# radiation.net
KiCad netlist of a schematic drawn in EAGLE
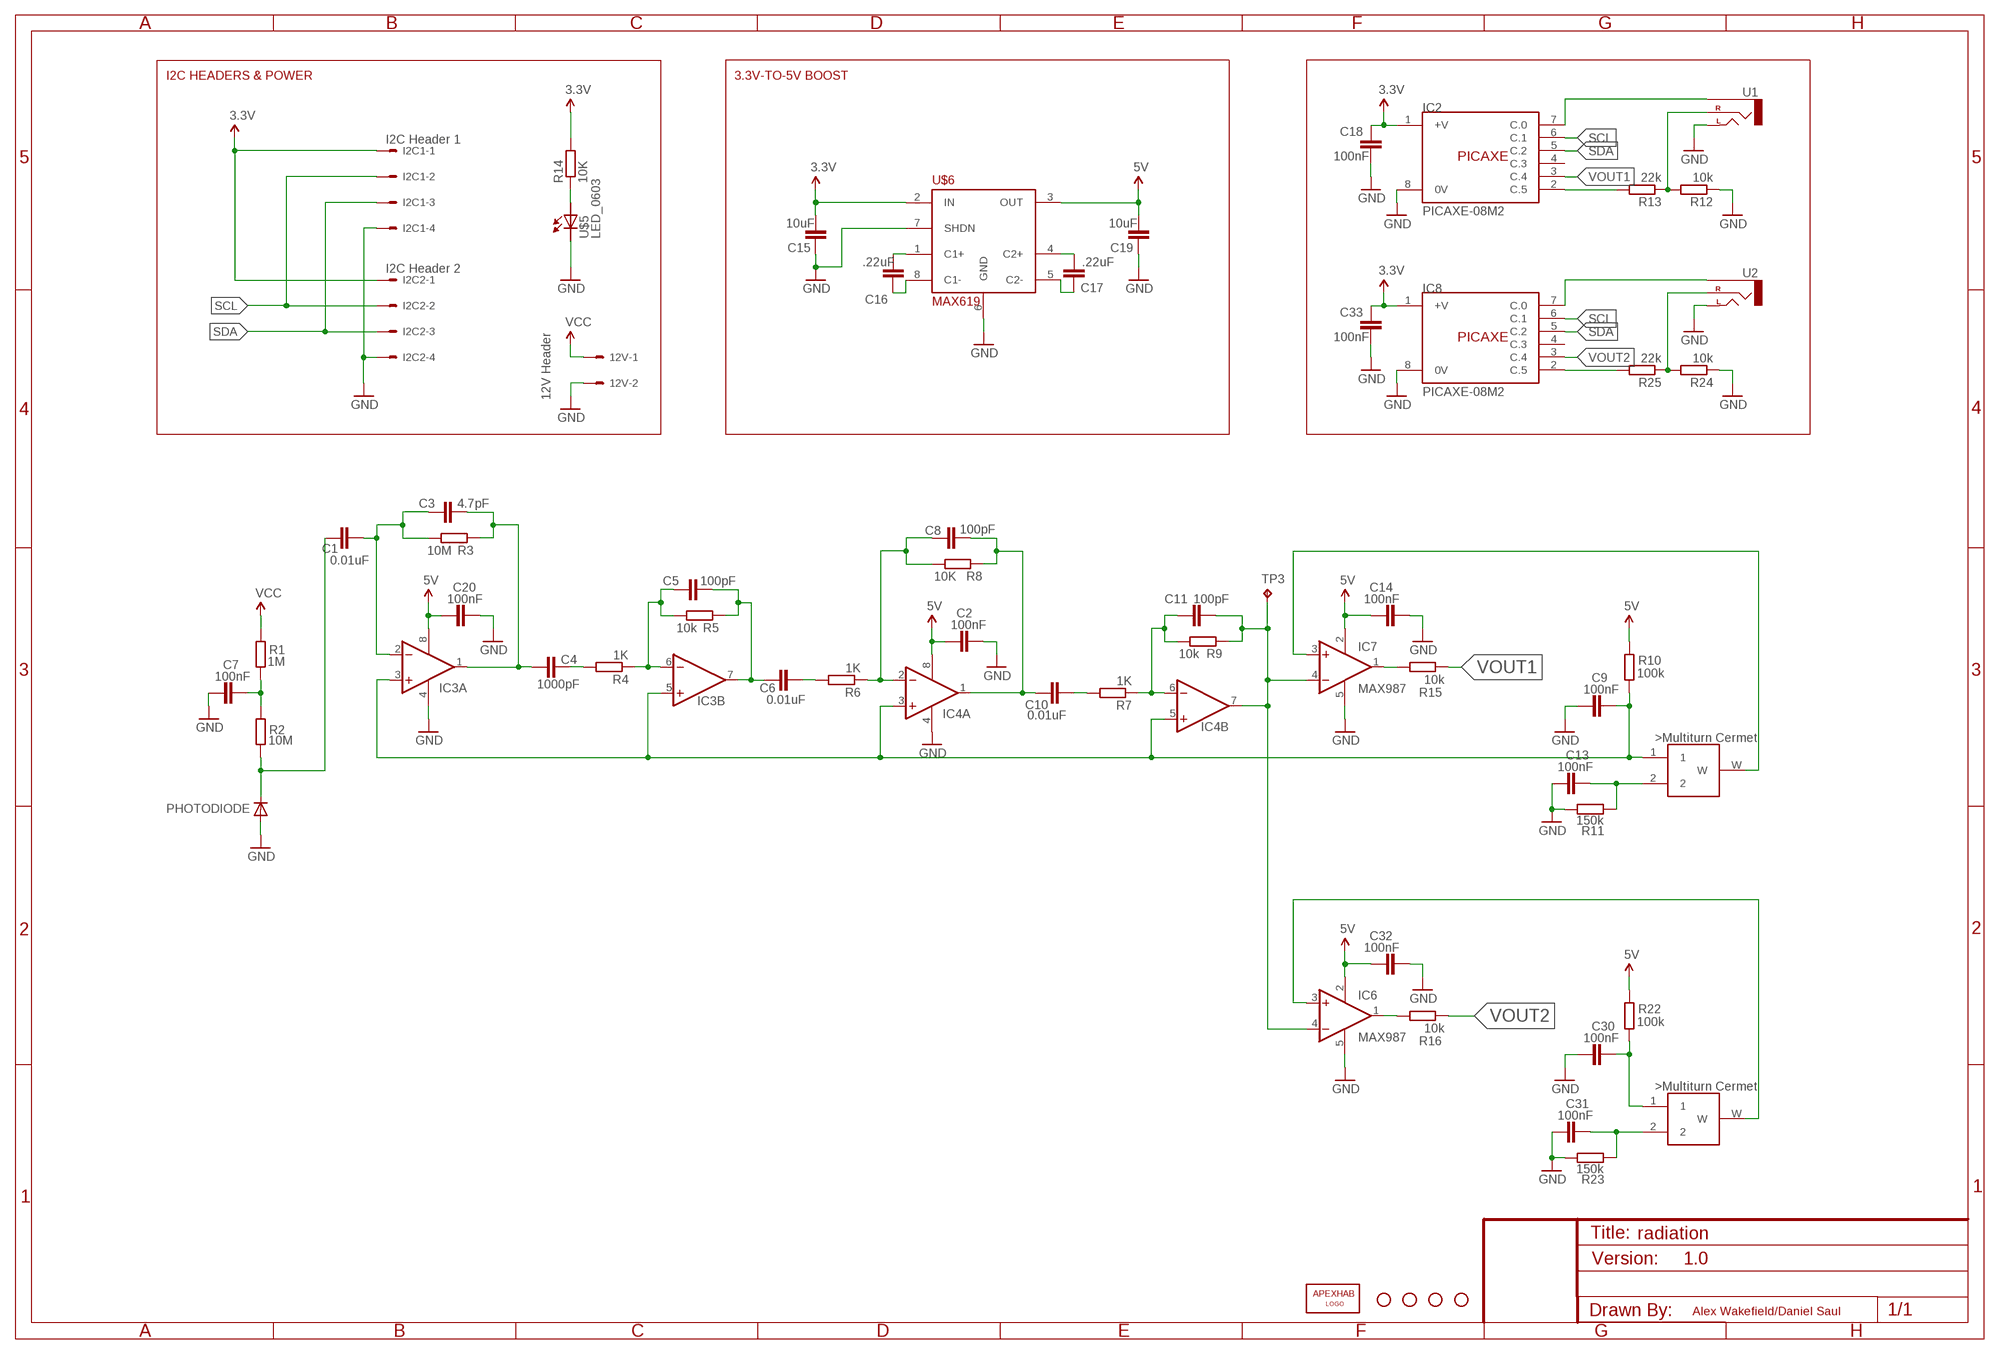
[diagram p0: schematic, sheet 1]

(export (version "E")
  (design (tool "Eeschema 10.0.6"))
  (components
    (comp (ref "12V")
      (value "12V Header")
      (footprint "eagle-import:6410-02")
      (libsource (lib "eagle-import") (part "22-?-0227-2021"))
    )
    (comp (ref "C1")
      (value "0.01uF")
      (footprint "eagle-import:C0805")
      (libsource (lib "eagle-import") (part "C-EUC0805"))
    )
    (comp (ref "C2")
      (value "100nF")
      (footprint "eagle-import:C0805")
      (libsource (lib "eagle-import") (part "C-EUC0805"))
    )
    (comp (ref "C3")
      (value "4.7pF")
      (footprint "eagle-import:C0805")
      (libsource (lib "eagle-import") (part "C-EUC0805"))
    )
    (comp (ref "C4")
      (value "1000pF")
      (footprint "eagle-import:C0805")
      (libsource (lib "eagle-import") (part "C-EUC0805"))
    )
    (comp (ref "C5")
      (value "100pF")
      (footprint "eagle-import:C0805")
      (libsource (lib "eagle-import") (part "C-EUC0805"))
    )
    (comp (ref "C6")
      (value "0.01uF")
      (footprint "eagle-import:C0805")
      (libsource (lib "eagle-import") (part "C-EUC0805"))
    )
    (comp (ref "C7")
      (value "100nF")
      (footprint "eagle-import:C0805")
      (libsource (lib "eagle-import") (part "C-EUC0805"))
    )
    (comp (ref "C8")
      (value "100pF")
      (footprint "eagle-import:C0805")
      (libsource (lib "eagle-import") (part "C-EUC0805"))
    )
    (comp (ref "C9")
      (value "100nF")
      (footprint "eagle-import:C0805")
      (libsource (lib "eagle-import") (part "C-EUC0805"))
    )
    (comp (ref "C10")
      (value "0.01uF")
      (footprint "eagle-import:C0805")
      (libsource (lib "eagle-import") (part "C-EUC0805"))
    )
    (comp (ref "C11")
      (value "100pF")
      (footprint "eagle-import:C0805")
      (libsource (lib "eagle-import") (part "C-EUC0805"))
    )
    (comp (ref "C13")
      (value "100nF")
      (footprint "eagle-import:C0805")
      (libsource (lib "eagle-import") (part "C-EUC0805"))
    )
    (comp (ref "C14")
      (value "100nF")
      (footprint "eagle-import:C0805")
      (libsource (lib "eagle-import") (part "C-EUC0805"))
    )
    (comp (ref "C15")
      (value "10uF")
      (footprint "eagle-import:C0805")
      (libsource (lib "eagle-import") (part "C-EUC0805"))
    )
    (comp (ref "C16")
      (value ".22uF")
      (footprint "eagle-import:C0805")
      (libsource (lib "eagle-import") (part "C-EUC0805"))
    )
    (comp (ref "C17")
      (value ".22uF")
      (footprint "eagle-import:C0805")
      (libsource (lib "eagle-import") (part "C-EUC0805"))
    )
    (comp (ref "C18")
      (value "100nF")
      (footprint "eagle-import:C0805")
      (libsource (lib "eagle-import") (part "C-EUC0805"))
    )
    (comp (ref "C19")
      (value "10uF")
      (footprint "eagle-import:C0805")
      (libsource (lib "eagle-import") (part "C-EUC0805"))
    )
    (comp (ref "C20")
      (value "100nF")
      (footprint "eagle-import:C0805")
      (libsource (lib "eagle-import") (part "C-EUC0805"))
    )
    (comp (ref "C30")
      (value "100nF")
      (footprint "eagle-import:C0805")
      (libsource (lib "eagle-import") (part "C-EUC0805"))
    )
    (comp (ref "C31")
      (value "100nF")
      (footprint "eagle-import:C0805")
      (libsource (lib "eagle-import") (part "C-EUC0805"))
    )
    (comp (ref "C32")
      (value "100nF")
      (footprint "eagle-import:C0805")
      (libsource (lib "eagle-import") (part "C-EUC0805"))
    )
    (comp (ref "C33")
      (value "100nF")
      (footprint "eagle-import:C0805")
      (libsource (lib "eagle-import") (part "C-EUC0805"))
    )
    (comp (ref "I2C1")
      (value "I2C Header 1")
      (footprint "eagle-import:6410-04")
      (libsource (lib "eagle-import") (part "22-?-0427-2041"))
    )
    (comp (ref "I2C2")
      (value "I2C Header 2")
      (footprint "eagle-import:6410-04")
      (libsource (lib "eagle-import") (part "22-?-0427-2041"))
    )
    (comp (ref "IC2")
      (value "PICAXE-08M2")
      (footprint "eagle-import:SOIC8")
      (libsource (lib "eagle-import") (part "PICAXE-08M2"))
    )
    (comp (ref "IC3")
      (value "max4477")
      (footprint "eagle-import:SO08")
      (libsource (lib "eagle-import") (part "CA3240ED"))
    )
    (comp (ref "IC4")
      (value "<AX4477")
      (footprint "eagle-import:SO08")
      (libsource (lib "eagle-import") (part "CA3240ED"))
    )
    (comp (ref "IC6")
      (value "MAX987")
      (footprint "eagle-import:SOT23-5")
      (libsource (lib "eagle-import") (part "MCP601R"))
    )
    (comp (ref "IC7")
      (value "MAX987")
      (footprint "eagle-import:SOT23-5")
      (libsource (lib "eagle-import") (part "MCP601R"))
    )
    (comp (ref "IC8")
      (value "PICAXE-08M2")
      (footprint "eagle-import:SOIC8")
      (libsource (lib "eagle-import") (part "PICAXE-08M2"))
    )
    (comp (ref "JP1")
      (value "APEXHAB-LOGO_APEX")
      (footprint "eagle-import:APEX-LOGO")
      (libsource (lib "eagle-import") (part "APEXHAB-LOGO_APEX"))
    )
    (comp (ref "JP2")
      (value "STAND-OFF")
      (footprint "eagle-import:STAND-OFF")
      (libsource (lib "eagle-import") (part "STAND-OFF"))
    )
    (comp (ref "JP3")
      (value "STAND-OFF")
      (footprint "eagle-import:STAND-OFF")
      (libsource (lib "eagle-import") (part "STAND-OFF"))
    )
    (comp (ref "JP4")
      (value "STAND-OFF")
      (footprint "eagle-import:STAND-OFF")
      (libsource (lib "eagle-import") (part "STAND-OFF"))
    )
    (comp (ref "JP5")
      (value "STAND-OFF")
      (footprint "eagle-import:STAND-OFF")
      (libsource (lib "eagle-import") (part "STAND-OFF"))
    )
    (comp (ref "PHOTODIODE")
      (value "DIODE-D-2.5")
      (footprint "eagle-import:D-2.5")
      (libsource (lib "eagle-import") (part "DIODE-D-2.5"))
    )
    (comp (ref "R1")
      (value "1M")
      (footprint "eagle-import:R0805")
      (libsource (lib "eagle-import") (part "R-EU_R0805"))
    )
    (comp (ref "R2")
      (value "10M")
      (footprint "eagle-import:R0805")
      (libsource (lib "eagle-import") (part "R-EU_R0805"))
    )
    (comp (ref "R3")
      (value "10M")
      (footprint "eagle-import:R0805")
      (libsource (lib "eagle-import") (part "R-EU_R0805"))
    )
    (comp (ref "R4")
      (value "1K")
      (footprint "eagle-import:R0805")
      (libsource (lib "eagle-import") (part "R-EU_R0805"))
    )
    (comp (ref "R5")
      (value "10k")
      (footprint "eagle-import:R0805")
      (libsource (lib "eagle-import") (part "R-EU_R0805"))
    )
    (comp (ref "R6")
      (value "1K")
      (footprint "eagle-import:R0805")
      (libsource (lib "eagle-import") (part "R-EU_R0805"))
    )
    (comp (ref "R7")
      (value "1K")
      (footprint "eagle-import:R0805")
      (libsource (lib "eagle-import") (part "R-EU_R0805"))
    )
    (comp (ref "R8")
      (value "10K")
      (footprint "eagle-import:R0805")
      (libsource (lib "eagle-import") (part "R-EU_R0805"))
    )
    (comp (ref "R9")
      (value "10k")
      (footprint "eagle-import:R0805")
      (libsource (lib "eagle-import") (part "R-EU_R0805"))
    )
    (comp (ref "R10")
      (value "100k")
      (footprint "eagle-import:R0805")
      (libsource (lib "eagle-import") (part "R-EU_R0805"))
    )
    (comp (ref "R11")
      (value "150k")
      (footprint "eagle-import:R0805")
      (libsource (lib "eagle-import") (part "R-EU_R0805"))
    )
    (comp (ref "R12")
      (value "10k")
      (footprint "eagle-import:R0805")
      (libsource (lib "eagle-import") (part "R-EU_R0805"))
    )
    (comp (ref "R13")
      (value "22k")
      (footprint "eagle-import:R0805")
      (libsource (lib "eagle-import") (part "R-EU_R0805"))
    )
    (comp (ref "R14")
      (value "10K")
      (footprint "eagle-import:R0805")
      (libsource (lib "eagle-import") (part "R-EU_R0805"))
    )
    (comp (ref "R15")
      (value "10k")
      (footprint "eagle-import:R0805")
      (libsource (lib "eagle-import") (part "R-EU_R0805"))
    )
    (comp (ref "R16")
      (value "10k")
      (footprint "eagle-import:R0805")
      (libsource (lib "eagle-import") (part "R-EU_R0805"))
    )
    (comp (ref "R22")
      (value "100k")
      (footprint "eagle-import:R0805")
      (libsource (lib "eagle-import") (part "R-EU_R0805"))
    )
    (comp (ref "R23")
      (value "150k")
      (footprint "eagle-import:R0805")
      (libsource (lib "eagle-import") (part "R-EU_R0805"))
    )
    (comp (ref "R24")
      (value "10k")
      (footprint "eagle-import:R0805")
      (libsource (lib "eagle-import") (part "R-EU_R0805"))
    )
    (comp (ref "R25")
      (value "22k")
      (footprint "eagle-import:R0805")
      (libsource (lib "eagle-import") (part "R-EU_R0805"))
    )
    (comp (ref "TP3")
      (value "TPTP10SQ")
      (footprint "eagle-import:TP10SQ")
      (libsource (lib "eagle-import") (part "TPTP10SQ"))
    )
    (comp (ref "U$3")
      (value "YL_SMT_11-TURN_CERMET_TRIMMER,_10K_0.25W")
      (footprint "eagle-import:YL_SMT_11-TURN_CERMET_TRIMMER,_10K_0.25W")
      (libsource (lib "eagle-import") (part "YL_SMT_11-TURN_CERMET_TRIMMER,_10K_0.25W"))
    )
    (comp (ref "U$4")
      (value "YL_SMT_11-TURN_CERMET_TRIMMER,_10K_0.25W")
      (footprint "eagle-import:YL_SMT_11-TURN_CERMET_TRIMMER,_10K_0.25W")
      (libsource (lib "eagle-import") (part "YL_SMT_11-TURN_CERMET_TRIMMER,_10K_0.25W"))
    )
    (comp (ref "U$5")
      (value "LED_0603")
      (footprint "eagle-import:CHIPLED_0603")
      (libsource (lib "eagle-import") (part "LED_0603"))
    )
    (comp (ref "U$6")
      (value "MAX619")
      (footprint "eagle-import:SO8")
      (libsource (lib "eagle-import") (part "MAX619"))
    )
    (comp (ref "U1")
      (value "AUDIO-JACKPTH")
      (footprint "eagle-import:AUDIO-JACK")
      (libsource (lib "eagle-import") (part "AUDIO-JACKPTH"))
    )
    (comp (ref "U2")
      (value "AUDIO-JACKPTH")
      (footprint "eagle-import:AUDIO-JACK")
      (libsource (lib "eagle-import") (part "AUDIO-JACKPTH"))
    )
  )
  (nets
    (net (code "1") (name "3.3V") (class "Default")
      (node (ref "C15") (pin "2") (pinfunction "2_2") (pintype "passive"))
      (node (ref "C18") (pin "1") (pinfunction "1_1") (pintype "passive"))
      (node (ref "C33") (pin "1") (pinfunction "1_1") (pintype "passive"))
      (node (ref "I2C1") (pin "1") (pinfunction "S_1") (pintype "passive"))
      (node (ref "I2C2") (pin "1") (pinfunction "S_1") (pintype "passive"))
      (node (ref "IC2") (pin "1") (pinfunction "+V_1") (pintype "power_in"))
      (node (ref "IC8") (pin "1") (pinfunction "+V_1") (pintype "power_in"))
      (node (ref "R14") (pin "2") (pinfunction "2_2") (pintype "passive"))
      (node (ref "U$6") (pin "2") (pinfunction "IN_2") (pintype "bidirectional"))
    )
    (net (code "2") (name "5V") (class "Default")
      (node (ref "C14") (pin "1") (pinfunction "1_1") (pintype "passive"))
      (node (ref "C19") (pin "2") (pinfunction "2_2") (pintype "passive"))
      (node (ref "C2") (pin "1") (pinfunction "1_1") (pintype "passive"))
      (node (ref "C20") (pin "1") (pinfunction "1_1") (pintype "passive"))
      (node (ref "C32") (pin "1") (pinfunction "1_1") (pintype "passive"))
      (node (ref "IC3") (pin "8") (pinfunction "V+_8") (pintype "power_in"))
      (node (ref "IC4") (pin "8") (pinfunction "V+_8") (pintype "power_in"))
      (node (ref "IC6") (pin "2") (pinfunction "V+_2") (pintype "power_in"))
      (node (ref "IC7") (pin "2") (pinfunction "V+_2") (pintype "power_in"))
      (node (ref "R10") (pin "1") (pinfunction "1_1") (pintype "passive"))
      (node (ref "R22") (pin "1") (pinfunction "1_1") (pintype "passive"))
      (node (ref "U$6") (pin "3") (pinfunction "OUT_3") (pintype "bidirectional"))
    )
    (net (code "3") (name "GND") (class "Default")
      (node (ref "12V") (pin "2") (pinfunction "S_2") (pintype "passive"))
      (node (ref "C13") (pin "1") (pinfunction "1_1") (pintype "passive"))
      (node (ref "C14") (pin "2") (pinfunction "2_2") (pintype "passive"))
      (node (ref "C15") (pin "1") (pinfunction "1_1") (pintype "passive"))
      (node (ref "C18") (pin "2") (pinfunction "2_2") (pintype "passive"))
      (node (ref "C19") (pin "1") (pinfunction "1_1") (pintype "passive"))
      (node (ref "C2") (pin "2") (pinfunction "2_2") (pintype "passive"))
      (node (ref "C20") (pin "2") (pinfunction "2_2") (pintype "passive"))
      (node (ref "C30") (pin "1") (pinfunction "1_1") (pintype "passive"))
      (node (ref "C31") (pin "1") (pinfunction "1_1") (pintype "passive"))
      (node (ref "C32") (pin "2") (pinfunction "2_2") (pintype "passive"))
      (node (ref "C33") (pin "2") (pinfunction "2_2") (pintype "passive"))
      (node (ref "C7") (pin "1") (pinfunction "1_1") (pintype "passive"))
      (node (ref "C9") (pin "1") (pinfunction "1_1") (pintype "passive"))
      (node (ref "I2C1") (pin "4") (pinfunction "S_4") (pintype "passive"))
      (node (ref "I2C2") (pin "4") (pinfunction "S_4") (pintype "passive"))
      (node (ref "IC2") (pin "8") (pinfunction "0V_8") (pintype "power_in"))
      (node (ref "IC3") (pin "4") (pinfunction "V-_4") (pintype "power_in"))
      (node (ref "IC4") (pin "4") (pinfunction "V-_4") (pintype "power_in"))
      (node (ref "IC6") (pin "5") (pinfunction "V-_5") (pintype "power_in"))
      (node (ref "IC7") (pin "5") (pinfunction "V-_5") (pintype "power_in"))
      (node (ref "IC8") (pin "8") (pinfunction "0V_8") (pintype "power_in"))
      (node (ref "PHOTODIODE") (pin "A") (pinfunction "A_A") (pintype "passive"))
      (node (ref "R11") (pin "2") (pinfunction "2_2") (pintype "passive"))
      (node (ref "R12") (pin "1") (pinfunction "1_1") (pintype "passive"))
      (node (ref "R23") (pin "2") (pinfunction "2_2") (pintype "passive"))
      (node (ref "R24") (pin "1") (pinfunction "1_1") (pintype "passive"))
      (node (ref "U$5") (pin "C") (pinfunction "C_C") (pintype "passive"))
      (node (ref "U$6") (pin "6") (pinfunction "GND_6") (pintype "bidirectional"))
      (node (ref "U$6") (pin "7") (pinfunction "SHDN_7") (pintype "bidirectional"))
      (node (ref "U1") (pin "TIP") (pinfunction "LEFT_TIP") (pintype "bidirectional"))
      (node (ref "U2") (pin "TIP") (pinfunction "LEFT_TIP") (pintype "bidirectional"))
    )
    (net (code "4") (name "Net-(C1-Pad1)") (class "Default")
      (node (ref "C1") (pin "1") (pinfunction "1_1") (pintype "passive"))
      (node (ref "PHOTODIODE") (pin "C") (pinfunction "C_C") (pintype "passive"))
      (node (ref "R2") (pin "1") (pinfunction "1_1") (pintype "passive"))
    )
    (net (code "5") (name "Net-(C4-Pad2)") (class "Default")
      (node (ref "C4") (pin "2") (pinfunction "2_2") (pintype "passive"))
      (node (ref "R4") (pin "2") (pinfunction "2_2") (pintype "passive"))
    )
    (net (code "6") (name "Net-(C6-Pad2)") (class "Default")
      (node (ref "C6") (pin "2") (pinfunction "2_2") (pintype "passive"))
      (node (ref "R6") (pin "2") (pinfunction "2_2") (pintype "passive"))
    )
    (net (code "7") (name "Net-(C7-Pad2)") (class "Default")
      (node (ref "C7") (pin "2") (pinfunction "2_2") (pintype "passive"))
      (node (ref "R1") (pin "1") (pinfunction "1_1") (pintype "passive"))
      (node (ref "R2") (pin "2") (pinfunction "2_2") (pintype "passive"))
    )
    (net (code "8") (name "Net-(C10-Pad2)") (class "Default")
      (node (ref "C10") (pin "2") (pinfunction "2_2") (pintype "passive"))
      (node (ref "R7") (pin "2") (pinfunction "2_2") (pintype "passive"))
    )
    (net (code "9") (name "Net-(C13-Pad2)") (class "Default")
      (node (ref "C13") (pin "2") (pinfunction "2_2") (pintype "passive"))
      (node (ref "R11") (pin "1") (pinfunction "1_1") (pintype "passive"))
      (node (ref "U$4") (pin "2") (pinfunction "2_2") (pintype "bidirectional"))
    )
    (net (code "10") (name "Net-(C30-Pad2)") (class "Default")
      (node (ref "C30") (pin "2") (pinfunction "2_2") (pintype "passive"))
      (node (ref "R22") (pin "2") (pinfunction "2_2") (pintype "passive"))
      (node (ref "U$3") (pin "1") (pinfunction "1_1") (pintype "bidirectional"))
    )
    (net (code "11") (name "Net-(C31-Pad2)") (class "Default")
      (node (ref "C31") (pin "2") (pinfunction "2_2") (pintype "passive"))
      (node (ref "R23") (pin "1") (pinfunction "1_1") (pintype "passive"))
      (node (ref "U$3") (pin "2") (pinfunction "2_2") (pintype "bidirectional"))
    )
    (net (code "12") (name "Net-(IC2-C.0)") (class "Default")
      (node (ref "IC2") (pin "7") (pinfunction "C.0_7") (pintype "bidirectional"))
      (node (ref "U1") (pin "SLEEVE") (pinfunction "SLEEVE_SLEEVE") (pintype "bidirectional"))
    )
    (net (code "13") (name "Net-(IC2-C.5)") (class "Default")
      (node (ref "IC2") (pin "2") (pinfunction "C.5_2") (pintype "bidirectional"))
      (node (ref "R13") (pin "2") (pinfunction "2_2") (pintype "passive"))
    )
    (net (code "14") (name "Net-(IC3A-+IN)") (class "Default")
      (node (ref "C9") (pin "2") (pinfunction "2_2") (pintype "passive"))
      (node (ref "IC3") (pin "3") (pinfunction "+IN_3") (pintype "input"))
      (node (ref "IC3") (pin "5") (pinfunction "+IN_5") (pintype "input"))
      (node (ref "IC4") (pin "3") (pinfunction "+IN_3") (pintype "input"))
      (node (ref "IC4") (pin "5") (pinfunction "+IN_5") (pintype "input"))
      (node (ref "R10") (pin "2") (pinfunction "2_2") (pintype "passive"))
      (node (ref "U$4") (pin "1") (pinfunction "1_1") (pintype "bidirectional"))
    )
    (net (code "15") (name "Net-(IC3A--IN)") (class "Default")
      (node (ref "C1") (pin "2") (pinfunction "2_2") (pintype "passive"))
      (node (ref "C3") (pin "1") (pinfunction "1_1") (pintype "passive"))
      (node (ref "IC3") (pin "2") (pinfunction "-IN_2") (pintype "input"))
      (node (ref "R3") (pin "2") (pinfunction "2_2") (pintype "passive"))
    )
    (net (code "16") (name "Net-(IC3A-OUT)") (class "Default")
      (node (ref "C3") (pin "2") (pinfunction "2_2") (pintype "passive"))
      (node (ref "C4") (pin "1") (pinfunction "1_1") (pintype "passive"))
      (node (ref "IC3") (pin "1") (pinfunction "OUT_1") (pintype "output"))
      (node (ref "R3") (pin "1") (pinfunction "1_1") (pintype "passive"))
    )
    (net (code "17") (name "Net-(IC3B--IN)") (class "Default")
      (node (ref "C5") (pin "1") (pinfunction "1_1") (pintype "passive"))
      (node (ref "IC3") (pin "6") (pinfunction "-IN_6") (pintype "input"))
      (node (ref "R4") (pin "1") (pinfunction "1_1") (pintype "passive"))
      (node (ref "R5") (pin "2") (pinfunction "2_2") (pintype "passive"))
    )
    (net (code "18") (name "Net-(IC3B-OUT)") (class "Default")
      (node (ref "C5") (pin "2") (pinfunction "2_2") (pintype "passive"))
      (node (ref "C6") (pin "1") (pinfunction "1_1") (pintype "passive"))
      (node (ref "IC3") (pin "7") (pinfunction "OUT_7") (pintype "output"))
      (node (ref "R5") (pin "1") (pinfunction "1_1") (pintype "passive"))
    )
    (net (code "19") (name "Net-(IC4A--IN)") (class "Default")
      (node (ref "C8") (pin "1") (pinfunction "1_1") (pintype "passive"))
      (node (ref "IC4") (pin "2") (pinfunction "-IN_2") (pintype "input"))
      (node (ref "R6") (pin "1") (pinfunction "1_1") (pintype "passive"))
      (node (ref "R8") (pin "2") (pinfunction "2_2") (pintype "passive"))
    )
    (net (code "20") (name "Net-(IC4A-OUT)") (class "Default")
      (node (ref "C10") (pin "1") (pinfunction "1_1") (pintype "passive"))
      (node (ref "C8") (pin "2") (pinfunction "2_2") (pintype "passive"))
      (node (ref "IC4") (pin "1") (pinfunction "OUT_1") (pintype "output"))
      (node (ref "R8") (pin "1") (pinfunction "1_1") (pintype "passive"))
    )
    (net (code "21") (name "Net-(IC4B--IN)") (class "Default")
      (node (ref "C11") (pin "1") (pinfunction "1_1") (pintype "passive"))
      (node (ref "IC4") (pin "6") (pinfunction "-IN_6") (pintype "input"))
      (node (ref "R7") (pin "1") (pinfunction "1_1") (pintype "passive"))
      (node (ref "R9") (pin "2") (pinfunction "2_2") (pintype "passive"))
    )
    (net (code "22") (name "Net-(IC4B-OUT)") (class "Default")
      (node (ref "C11") (pin "2") (pinfunction "2_2") (pintype "passive"))
      (node (ref "IC4") (pin "7") (pinfunction "OUT_7") (pintype "output"))
      (node (ref "IC6") (pin "4") (pinfunction "-IN_4") (pintype "input"))
      (node (ref "IC7") (pin "4") (pinfunction "-IN_4") (pintype "input"))
      (node (ref "R9") (pin "1") (pinfunction "1_1") (pintype "passive"))
      (node (ref "TP3") (pin "TP") (pinfunction "TP_TP") (pintype "input"))
    )
    (net (code "23") (name "Net-(IC6-+IN)") (class "Default")
      (node (ref "IC6") (pin "3") (pinfunction "+IN_3") (pintype "input"))
      (node (ref "U$3") (pin "W") (pinfunction "W_W") (pintype "bidirectional"))
    )
    (net (code "24") (name "Net-(IC6-OUT)") (class "Default")
      (node (ref "IC6") (pin "1") (pinfunction "OUT_1") (pintype "output"))
      (node (ref "R16") (pin "2") (pinfunction "2_2") (pintype "passive"))
    )
    (net (code "25") (name "Net-(IC7-+IN)") (class "Default")
      (node (ref "IC7") (pin "3") (pinfunction "+IN_3") (pintype "input"))
      (node (ref "U$4") (pin "W") (pinfunction "W_W") (pintype "bidirectional"))
    )
    (net (code "26") (name "Net-(IC7-OUT)") (class "Default")
      (node (ref "IC7") (pin "1") (pinfunction "OUT_1") (pintype "output"))
      (node (ref "R15") (pin "2") (pinfunction "2_2") (pintype "passive"))
    )
    (net (code "27") (name "Net-(IC8-C.0)") (class "Default")
      (node (ref "IC8") (pin "7") (pinfunction "C.0_7") (pintype "bidirectional"))
      (node (ref "U2") (pin "SLEEVE") (pinfunction "SLEEVE_SLEEVE") (pintype "bidirectional"))
    )
    (net (code "28") (name "Net-(IC8-C.5)") (class "Default")
      (node (ref "IC8") (pin "2") (pinfunction "C.5_2") (pintype "bidirectional"))
      (node (ref "R25") (pin "2") (pinfunction "2_2") (pintype "passive"))
    )
    (net (code "29") (name "Net-(R14-Pad1)") (class "Default")
      (node (ref "R14") (pin "1") (pinfunction "1_1") (pintype "passive"))
      (node (ref "U$5") (pin "A") (pinfunction "A_A") (pintype "passive"))
    )
    (net (code "30") (name "Net-(U$6-C1+)") (class "Default")
      (node (ref "C16") (pin "2") (pinfunction "2_2") (pintype "passive"))
      (node (ref "U$6") (pin "1") (pinfunction "C1+_1") (pintype "bidirectional"))
    )
    (net (code "31") (name "Net-(U$6-C1-)") (class "Default")
      (node (ref "C16") (pin "1") (pinfunction "1_1") (pintype "passive"))
      (node (ref "U$6") (pin "8") (pinfunction "C1-_8") (pintype "bidirectional"))
    )
    (net (code "32") (name "Net-(U$6-C2+)") (class "Default")
      (node (ref "C17") (pin "2") (pinfunction "2_2") (pintype "passive"))
      (node (ref "U$6") (pin "4") (pinfunction "C2+_4") (pintype "bidirectional"))
    )
    (net (code "33") (name "Net-(U$6-C2-)") (class "Default")
      (node (ref "C17") (pin "1") (pinfunction "1_1") (pintype "passive"))
      (node (ref "U$6") (pin "5") (pinfunction "C2-_5") (pintype "bidirectional"))
    )
    (net (code "34") (name "Net-(U1-RIGHT)") (class "Default")
      (node (ref "R12") (pin "2") (pinfunction "2_2") (pintype "passive"))
      (node (ref "R13") (pin "1") (pinfunction "1_1") (pintype "passive"))
      (node (ref "U1") (pin "RING") (pinfunction "RIGHT_RING") (pintype "bidirectional"))
    )
    (net (code "35") (name "Net-(U2-RIGHT)") (class "Default")
      (node (ref "R24") (pin "2") (pinfunction "2_2") (pintype "passive"))
      (node (ref "R25") (pin "1") (pinfunction "1_1") (pintype "passive"))
      (node (ref "U2") (pin "RING") (pinfunction "RIGHT_RING") (pintype "bidirectional"))
    )
    (net (code "36") (name "SCL") (class "Default")
      (node (ref "I2C1") (pin "2") (pinfunction "S_2") (pintype "passive"))
      (node (ref "I2C2") (pin "2") (pinfunction "S_2") (pintype "passive"))
      (node (ref "IC2") (pin "6") (pinfunction "C.1_6") (pintype "bidirectional"))
      (node (ref "IC8") (pin "6") (pinfunction "C.1_6") (pintype "bidirectional"))
    )
    (net (code "37") (name "SDA") (class "Default")
      (node (ref "I2C1") (pin "3") (pinfunction "S_3") (pintype "passive"))
      (node (ref "I2C2") (pin "3") (pinfunction "S_3") (pintype "passive"))
      (node (ref "IC2") (pin "5") (pinfunction "C.2_5") (pintype "bidirectional"))
      (node (ref "IC8") (pin "5") (pinfunction "C.2_5") (pintype "bidirectional"))
    )
    (net (code "38") (name "VCC") (class "Default")
      (node (ref "12V") (pin "1") (pinfunction "S_1") (pintype "passive"))
      (node (ref "R1") (pin "2") (pinfunction "2_2") (pintype "passive"))
    )
    (net (code "39") (name "VOUT1") (class "Default")
      (node (ref "IC2") (pin "3") (pinfunction "C.4_3") (pintype "bidirectional"))
      (node (ref "R15") (pin "1") (pinfunction "1_1") (pintype "passive"))
    )
    (net (code "40") (name "VOUT2") (class "Default")
      (node (ref "IC8") (pin "3") (pinfunction "C.4_3") (pintype "bidirectional"))
      (node (ref "R16") (pin "1") (pinfunction "1_1") (pintype "passive"))
    )
    (net (code "41") (name "unconnected-(IC2-C.3-Pad4)") (class "Default")
      (node (ref "IC2") (pin "4") (pinfunction "C.3_4") (pintype "bidirectional"))
    )
    (net (code "42") (name "unconnected-(IC8-C.3-Pad4)") (class "Default")
      (node (ref "IC8") (pin "4") (pinfunction "C.3_4") (pintype "bidirectional"))
    )
  )
)
